# BLUETOOTH_nRF52382.net
KiCad netlist of a schematic drawn in Altium Designer
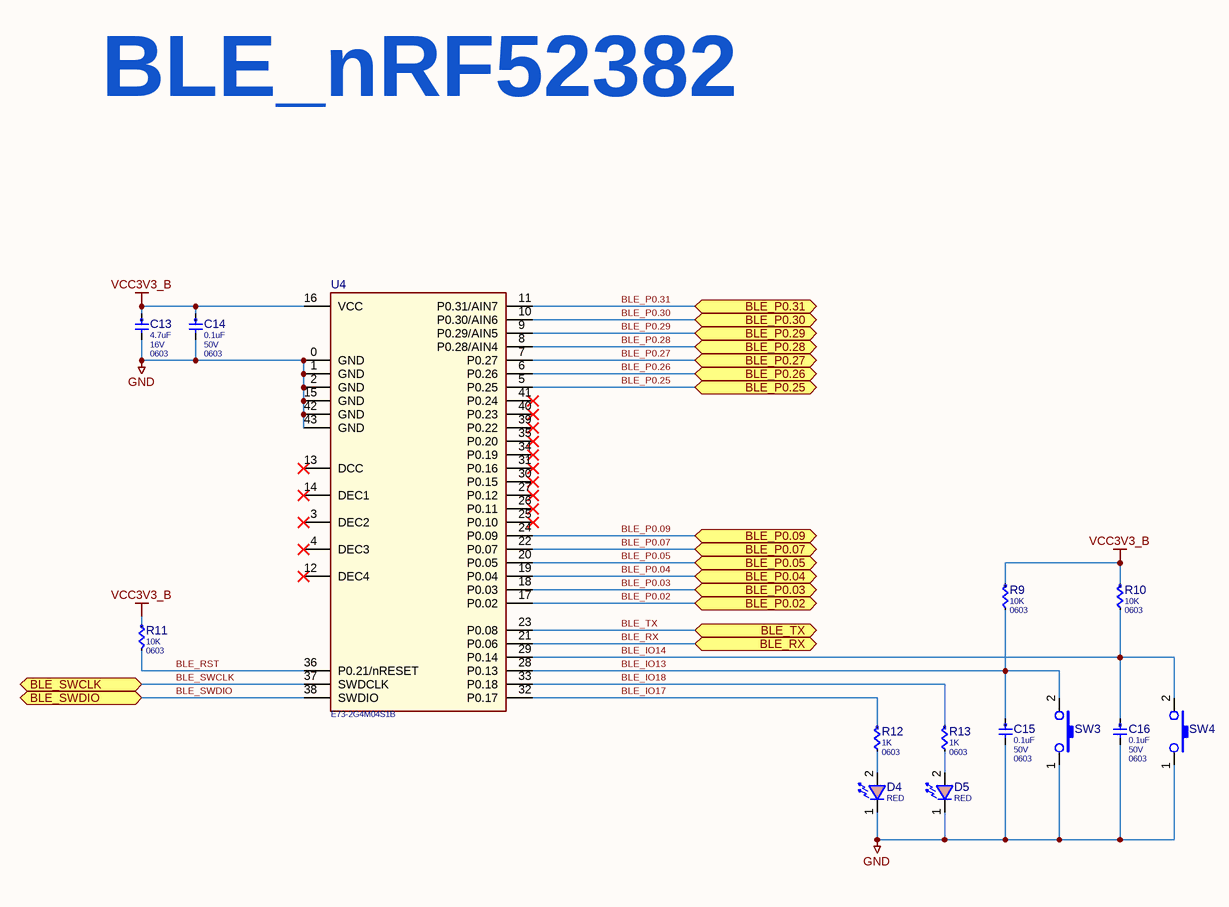
[diagram p0: BLUETOOTH_nRF52382.SchDoc]

(export (version "E")
  (design (tool "Eeschema 10.0.6"))
  (components
    (comp (ref "C13")
      (value "4.7uF")
      (footprint "C0603")
      (description "CAP CER 4.7UF 20% 16V X5R 0603 SMD")
      (fields
        (field (name "TOLERANCE") "20%")
        (field (name "VOLTAGE") "16V")
        (field (name "PACK") "0603")
        (field (name "Comment") "4.7uF 16V 0603")
      )
      (libsource (lib "FENIKAA_LIB") (part "C0603_4.7uF_16V_20%"))
    )
    (comp (ref "C14")
      (value "0.1uF")
      (footprint "C0603")
      (description "CAP CER 0.1UF 10% 50V X7R 0603 SMD")
      (fields
        (field (name "TOLERANCE") "10%")
        (field (name "VOLTAGE") "50V")
        (field (name "PACK") "0603")
        (field (name "Comment") "0.1uF 50V 0603")
      )
      (libsource (lib "FENIKAA_LIB") (part "C0603_0.1uF_50V_10%"))
    )
    (comp (ref "C15")
      (value "0.1uF")
      (footprint "C0603")
      (description "CAP CER 0.1UF 10% 50V X7R 0603 SMD")
      (fields
        (field (name "TOLERANCE") "10%")
        (field (name "VOLTAGE") "50V")
        (field (name "PACK") "0603")
        (field (name "Comment") "0.1uF 50V 0603")
      )
      (libsource (lib "FENIKAA_LIB") (part "C0603_0.1uF_50V_10%"))
    )
    (comp (ref "C16")
      (value "0.1uF")
      (footprint "C0603")
      (description "CAP CER 0.1UF 10% 50V X7R 0603 SMD")
      (fields
        (field (name "TOLERANCE") "10%")
        (field (name "VOLTAGE") "50V")
        (field (name "PACK") "0603")
        (field (name "Comment") "0.1uF 50V 0603")
      )
      (libsource (lib "FENIKAA_LIB") (part "C0603_0.1uF_50V_10%"))
    )
    (comp (ref "D4")
      (value "LH R974-LP-1")
      (footprint "LED0805_RED")
      (description "LED IND RED 1.8V 20mA 0805 SMD")
      (fields (field (name "COLOR") "RED"))
      (libsource (lib "FENIKAA_LIB") (part "LED0805_RED"))
    )
    (comp (ref "D5")
      (value "LH R974-LP-1")
      (footprint "LED0805_RED")
      (description "LED IND RED 1.8V 20mA 0805 SMD")
      (fields (field (name "COLOR") "RED"))
      (libsource (lib "FENIKAA_LIB") (part "LED0805_RED"))
    )
    (comp (ref "R9")
      (value "10K")
      (footprint "R0603")
      (description "RES CHP 10K 1% 1/10W 0603 SMD")
      (fields (field (name "POWER") "1/10W") (field (name "PACK") "0603") (field (name "TOLERANCE") "1%"))
      (libsource (lib "FENIKAA_LIB") (part "R0603_10K_1/10W_1%"))
    )
    (comp (ref "R10")
      (value "10K")
      (footprint "R0603")
      (description "RES CHP 10K 1% 1/10W 0603 SMD")
      (fields (field (name "POWER") "1/10W") (field (name "PACK") "0603") (field (name "TOLERANCE") "1%"))
      (libsource (lib "FENIKAA_LIB") (part "R0603_10K_1/10W_1%"))
    )
    (comp (ref "R11")
      (value "10K")
      (footprint "R0603")
      (description "RES CHP 10K 1% 1/10W 0603 SMD")
      (fields (field (name "POWER") "1/10W") (field (name "PACK") "0603") (field (name "TOLERANCE") "1%"))
      (libsource (lib "FENIKAA_LIB") (part "R0603_10K_1/10W_1%"))
    )
    (comp (ref "R12")
      (value "1K")
      (footprint "R0603")
      (description "RES CHP 1K 1% 1/10W 0603 SMD")
      (fields (field (name "POWER") "1/10W") (field (name "PACK") "0603") (field (name "TOLERANCE") "1%"))
      (libsource (lib "FENIKAA_LIB") (part "R0603_1K_1/10W_1%"))
    )
    (comp (ref "R13")
      (value "1K")
      (footprint "R0603")
      (description "RES CHP 1K 1% 1/10W 0603 SMD")
      (fields (field (name "POWER") "1/10W") (field (name "PACK") "0603") (field (name "TOLERANCE") "1%"))
      (libsource (lib "FENIKAA_LIB") (part "R0603_1K_1/10W_1%"))
    )
    (comp (ref "SW3")
      (value "BTN 3x6x5 SMD")
      (footprint "BTN_6L3W5H")
      (description "SWT BTN 3x6x5 SMD")
      (libsource (lib "FENIKAA_LIB") (part "SWT_BTN_3x6x5"))
    )
    (comp (ref "SW4")
      (value "BTN 3x6x5 SMD")
      (footprint "BTN_6L3W5H")
      (description "SWT BTN 3x6x5 SMD")
      (libsource (lib "FENIKAA_LIB") (part "SWT_BTN_3x6x5"))
    )
    (comp (ref "U4")
      (value "nRF52832")
      (footprint "E73-2G4M04S1B")
      (description "MDL RF TRX BLE4.2 E73-2G4M04S1B 28.7L17.5W2.6H SMD")
      (fields (field (name "VOLTAGE") "1.8V ~ 3.6V") (field (name "MGR PN") "E73-2G4M04S1B"))
      (libsource (lib "FENIKAA_LIB") (part "MDL_nRF52832"))
    )
  )
  (nets
    (net (code "1") (name "/BLE_IO13") (class "Default")
      (node (ref "C15") (pin "1") (pinfunction "1_1") (pintype "passive"))
      (node (ref "R9") (pin "2") (pinfunction "2_2") (pintype "passive"))
      (node (ref "SW3") (pin "2") (pinfunction "3,4_2") (pintype "passive"))
      (node (ref "U4") (pin "28") (pinfunction "P0.13_28") (pintype "passive"))
    )
    (net (code "2") (name "/BLE_IO14") (class "Default")
      (node (ref "C16") (pin "1") (pinfunction "1_1") (pintype "passive"))
      (node (ref "R10") (pin "2") (pinfunction "2_2") (pintype "passive"))
      (node (ref "SW4") (pin "2") (pinfunction "3,4_2") (pintype "passive"))
      (node (ref "U4") (pin "29") (pinfunction "P0.14_29") (pintype "passive"))
    )
    (net (code "3") (name "/BLE_IO17") (class "Default")
      (node (ref "R12") (pin "1") (pinfunction "1_1") (pintype "passive"))
      (node (ref "U4") (pin "32") (pinfunction "P0.17_32") (pintype "passive"))
    )
    (net (code "4") (name "/BLE_IO18") (class "Default")
      (node (ref "R13") (pin "1") (pinfunction "1_1") (pintype "passive"))
      (node (ref "U4") (pin "33") (pinfunction "P0.18_33") (pintype "passive"))
    )
    (net (code "5") (name "/BLE_P0.02") (class "Default")
      (node (ref "U4") (pin "17") (pinfunction "P0.02_17") (pintype "passive"))
    )
    (net (code "6") (name "/BLE_P0.03") (class "Default")
      (node (ref "U4") (pin "18") (pinfunction "P0.03_18") (pintype "passive"))
    )
    (net (code "7") (name "/BLE_P0.04") (class "Default")
      (node (ref "U4") (pin "19") (pinfunction "P0.04_19") (pintype "passive"))
    )
    (net (code "8") (name "/BLE_P0.05") (class "Default")
      (node (ref "U4") (pin "20") (pinfunction "P0.05_20") (pintype "passive"))
    )
    (net (code "9") (name "/BLE_P0.07") (class "Default")
      (node (ref "U4") (pin "22") (pinfunction "P0.07_22") (pintype "passive"))
    )
    (net (code "10") (name "/BLE_P0.09") (class "Default")
      (node (ref "U4") (pin "24") (pinfunction "P0.09_24") (pintype "passive"))
    )
    (net (code "11") (name "/BLE_P0.25") (class "Default")
      (node (ref "U4") (pin "5") (pinfunction "P0.25_5") (pintype "passive"))
    )
    (net (code "12") (name "/BLE_P0.26") (class "Default")
      (node (ref "U4") (pin "6") (pinfunction "P0.26_6") (pintype "passive"))
    )
    (net (code "13") (name "/BLE_P0.27") (class "Default")
      (node (ref "U4") (pin "7") (pinfunction "P0.27_7") (pintype "passive"))
    )
    (net (code "14") (name "/BLE_P0.28") (class "Default")
      (node (ref "U4") (pin "8") (pinfunction "P0.28/AIN4_8") (pintype "passive"))
    )
    (net (code "15") (name "/BLE_P0.29") (class "Default")
      (node (ref "U4") (pin "9") (pinfunction "P0.29/AIN5_9") (pintype "passive"))
    )
    (net (code "16") (name "/BLE_P0.30") (class "Default")
      (node (ref "U4") (pin "10") (pinfunction "P0.30/AIN6_10") (pintype "passive"))
    )
    (net (code "17") (name "/BLE_P0.31") (class "Default")
      (node (ref "U4") (pin "11") (pinfunction "P0.31/AIN7_11") (pintype "passive"))
    )
    (net (code "18") (name "/BLE_RST") (class "Default")
      (node (ref "R11") (pin "2") (pinfunction "2_2") (pintype "passive"))
      (node (ref "U4") (pin "36") (pinfunction "P0.21/nRESET_36") (pintype "passive"))
    )
    (net (code "19") (name "/BLE_RX") (class "Default")
      (node (ref "U4") (pin "21") (pinfunction "P0.06_21") (pintype "passive"))
    )
    (net (code "20") (name "/BLE_SWCLK") (class "Default")
      (node (ref "U4") (pin "37") (pinfunction "SWDCLK_37") (pintype "passive"))
    )
    (net (code "21") (name "/BLE_SWDIO") (class "Default")
      (node (ref "U4") (pin "38") (pinfunction "SWDIO_38") (pintype "passive"))
    )
    (net (code "22") (name "/BLE_TX") (class "Default")
      (node (ref "U4") (pin "23") (pinfunction "P0.08_23") (pintype "passive"))
    )
    (net (code "23") (name "GND") (class "Default")
      (node (ref "C13") (pin "2") (pinfunction "2_2") (pintype "passive"))
      (node (ref "C14") (pin "2") (pinfunction "2_2") (pintype "passive"))
      (node (ref "C15") (pin "2") (pinfunction "2_2") (pintype "passive"))
      (node (ref "C16") (pin "2") (pinfunction "2_2") (pintype "passive"))
      (node (ref "D4") (pin "1") (pinfunction "K_1") (pintype "passive"))
      (node (ref "D5") (pin "1") (pinfunction "K_1") (pintype "passive"))
      (node (ref "SW3") (pin "1") (pinfunction "1,2_1") (pintype "passive"))
      (node (ref "SW4") (pin "1") (pinfunction "1,2_1") (pintype "passive"))
      (node (ref "U4") (pin "0") (pinfunction "GND_0") (pintype "passive"))
      (node (ref "U4") (pin "1") (pinfunction "GND_1") (pintype "passive"))
      (node (ref "U4") (pin "15") (pinfunction "GND_15") (pintype "passive"))
      (node (ref "U4") (pin "2") (pinfunction "GND_2") (pintype "passive"))
      (node (ref "U4") (pin "42") (pinfunction "GND_42") (pintype "passive"))
      (node (ref "U4") (pin "43") (pinfunction "GND_43") (pintype "passive"))
    )
    (net (code "24") (name "Net-(D4-A)") (class "Default")
      (node (ref "D4") (pin "2") (pinfunction "A_2") (pintype "passive"))
      (node (ref "R12") (pin "2") (pinfunction "2_2") (pintype "passive"))
    )
    (net (code "25") (name "Net-(D5-A)") (class "Default")
      (node (ref "D5") (pin "2") (pinfunction "A_2") (pintype "passive"))
      (node (ref "R13") (pin "2") (pinfunction "2_2") (pintype "passive"))
    )
    (net (code "26") (name "VCC3V3_B") (class "Default")
      (node (ref "C13") (pin "1") (pinfunction "1_1") (pintype "passive"))
      (node (ref "C14") (pin "1") (pinfunction "1_1") (pintype "passive"))
      (node (ref "R10") (pin "1") (pinfunction "1_1") (pintype "passive"))
      (node (ref "R11") (pin "1") (pinfunction "1_1") (pintype "passive"))
      (node (ref "R9") (pin "1") (pinfunction "1_1") (pintype "passive"))
      (node (ref "U4") (pin "16") (pinfunction "VCC_16") (pintype "passive"))
    )
    (net (code "27") (name "unconnected-(U4-DCC-Pad13)") (class "Default")
      (node (ref "U4") (pin "13") (pinfunction "DCC_13") (pintype "passive+no_connect"))
    )
    (net (code "28") (name "unconnected-(U4-DEC1-Pad14)") (class "Default")
      (node (ref "U4") (pin "14") (pinfunction "DEC1_14") (pintype "passive+no_connect"))
    )
    (net (code "29") (name "unconnected-(U4-DEC2-Pad3)") (class "Default")
      (node (ref "U4") (pin "3") (pinfunction "DEC2_3") (pintype "passive+no_connect"))
    )
    (net (code "30") (name "unconnected-(U4-DEC3-Pad4)") (class "Default")
      (node (ref "U4") (pin "4") (pinfunction "DEC3_4") (pintype "passive+no_connect"))
    )
    (net (code "31") (name "unconnected-(U4-DEC4-Pad12)") (class "Default")
      (node (ref "U4") (pin "12") (pinfunction "DEC4_12") (pintype "passive+no_connect"))
    )
    (net (code "32") (name "unconnected-(U4-P0.10-Pad25)") (class "Default")
      (node (ref "U4") (pin "25") (pinfunction "P0.10_25") (pintype "passive+no_connect"))
    )
    (net (code "33") (name "unconnected-(U4-P0.11-Pad26)") (class "Default")
      (node (ref "U4") (pin "26") (pinfunction "P0.11_26") (pintype "passive+no_connect"))
    )
    (net (code "34") (name "unconnected-(U4-P0.12-Pad27)") (class "Default")
      (node (ref "U4") (pin "27") (pinfunction "P0.12_27") (pintype "passive+no_connect"))
    )
    (net (code "35") (name "unconnected-(U4-P0.15-Pad30)") (class "Default")
      (node (ref "U4") (pin "30") (pinfunction "P0.15_30") (pintype "passive+no_connect"))
    )
    (net (code "36") (name "unconnected-(U4-P0.16-Pad31)") (class "Default")
      (node (ref "U4") (pin "31") (pinfunction "P0.16_31") (pintype "passive+no_connect"))
    )
    (net (code "37") (name "unconnected-(U4-P0.19-Pad34)") (class "Default")
      (node (ref "U4") (pin "34") (pinfunction "P0.19_34") (pintype "passive+no_connect"))
    )
    (net (code "38") (name "unconnected-(U4-P0.20-Pad35)") (class "Default")
      (node (ref "U4") (pin "35") (pinfunction "P0.20_35") (pintype "passive+no_connect"))
    )
    (net (code "39") (name "unconnected-(U4-P0.22-Pad39)") (class "Default")
      (node (ref "U4") (pin "39") (pinfunction "P0.22_39") (pintype "passive+no_connect"))
    )
    (net (code "40") (name "unconnected-(U4-P0.23-Pad40)") (class "Default")
      (node (ref "U4") (pin "40") (pinfunction "P0.23_40") (pintype "passive+no_connect"))
    )
    (net (code "41") (name "unconnected-(U4-P0.24-Pad41)") (class "Default")
      (node (ref "U4") (pin "41") (pinfunction "P0.24_41") (pintype "passive+no_connect"))
    )
  )
)
